# SCH_Roboliga_2026_Futbol_2026-04-12.net
KiCad netlist of a schematic drawn in EasyEDA
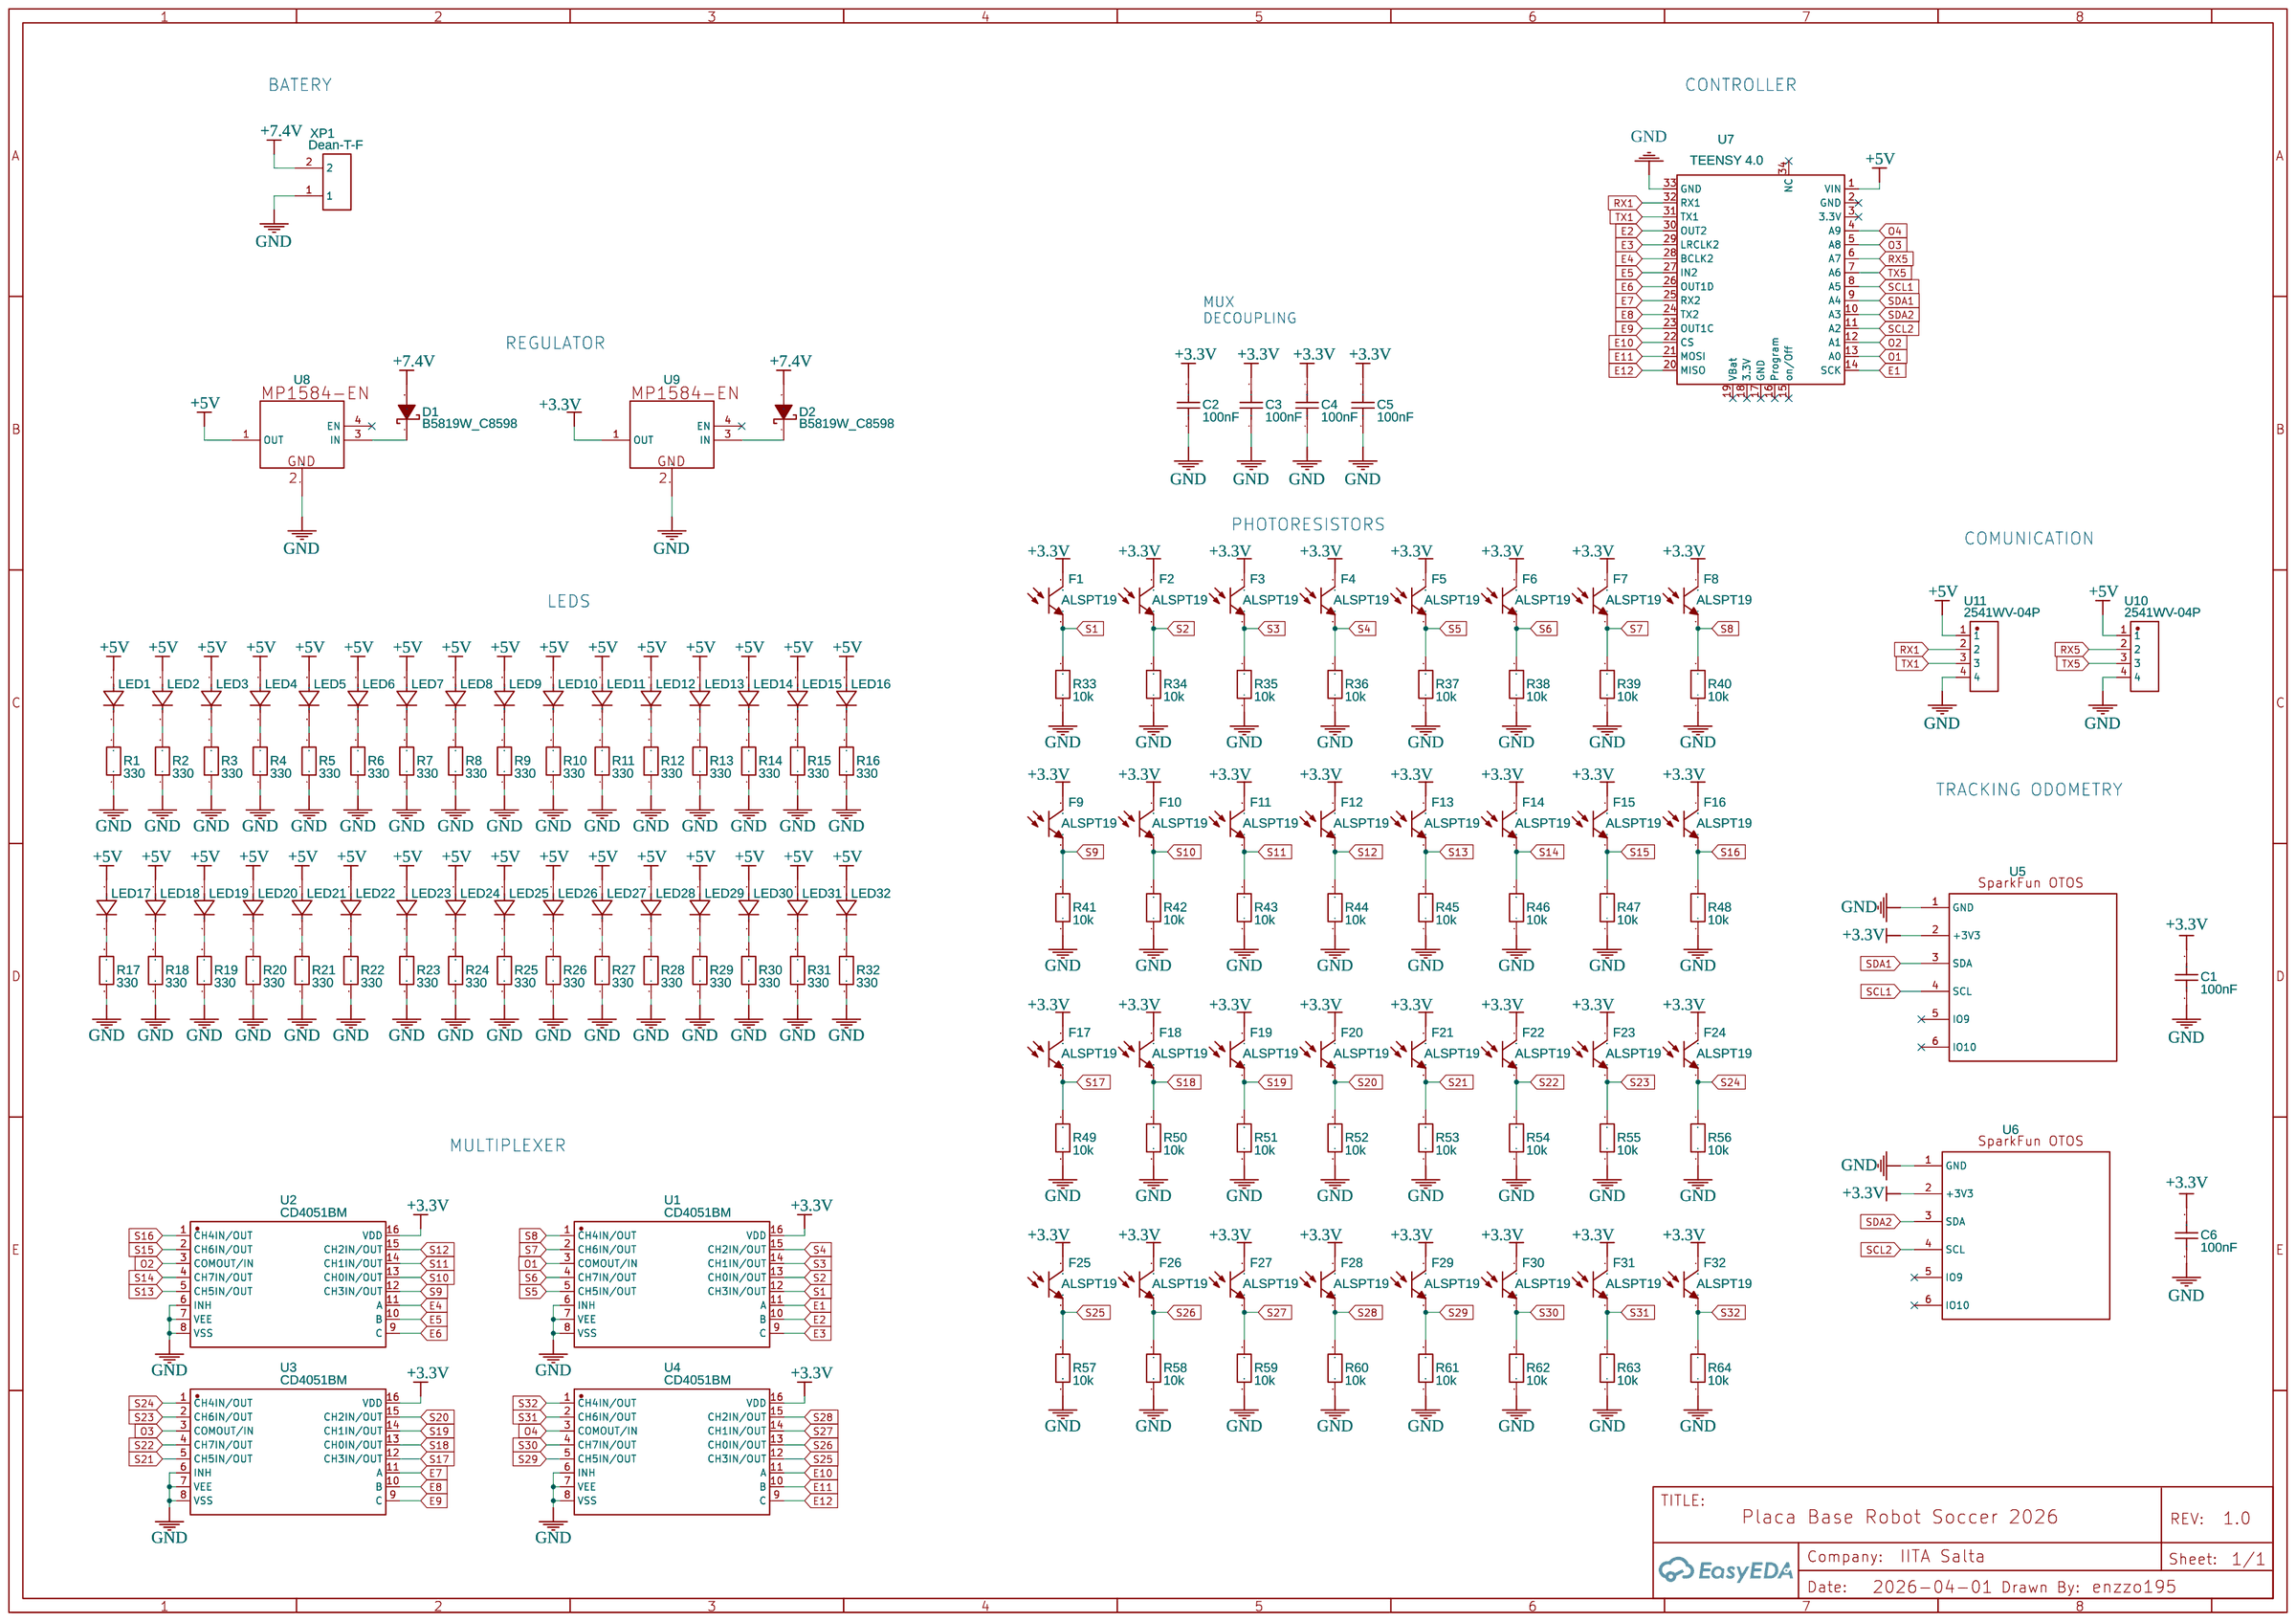
[diagram p0: schematic sheet]

(export (version "E")
  (design (tool "Eeschema 10.0.6"))
  (components
    (comp (ref "C1") (value "100nF") (libsource (lib "") (part "C_0603_US")))
    (comp (ref "C2") (value "100nF") (libsource (lib "") (part "C_0603_US")))
    (comp (ref "C3") (value "100nF") (libsource (lib "") (part "C_0603_US")))
    (comp (ref "C4") (value "100nF") (libsource (lib "") (part "C_0603_US")))
    (comp (ref "C5") (value "100nF") (libsource (lib "") (part "C_0603_US")))
    (comp (ref "C6") (value "100nF") (libsource (lib "") (part "C_0603_US")))
    (comp (ref "D1")
      (value "B5819W_C8598")
      (fields (field (name "Manufacturer Part") "B5819W SL") (field (name "Manufacturer") "CJ(江苏长电/长晶)"))
      (libsource (lib "") (part "B5819W_C8598"))
    )
    (comp (ref "D2")
      (value "B5819W_C8598")
      (fields (field (name "Manufacturer Part") "B5819W SL") (field (name "Manufacturer") "CJ(江苏长电/长晶)"))
      (libsource (lib "") (part "B5819W_C8598"))
    )
    (comp (ref "F1")
      (value "ALSPT19")
      (fields
        (field (name "Manufacturer Part") "ALS-PT19-315C/L177/TR8")
        (field (name "Manufacturer") "EVERLIGHT(亿光)")
      )
      (libsource (lib "") (part "ALS-PT19-315C/L177/TR8"))
    )
    (comp (ref "F2")
      (value "ALSPT19")
      (fields
        (field (name "Manufacturer Part") "ALS-PT19-315C/L177/TR8")
        (field (name "Manufacturer") "EVERLIGHT(亿光)")
      )
      (libsource (lib "") (part "ALS-PT19-315C/L177/TR8"))
    )
    (comp (ref "F3")
      (value "ALSPT19")
      (fields
        (field (name "Manufacturer Part") "ALS-PT19-315C/L177/TR8")
        (field (name "Manufacturer") "EVERLIGHT(亿光)")
      )
      (libsource (lib "") (part "ALS-PT19-315C/L177/TR8"))
    )
    (comp (ref "F4")
      (value "ALSPT19")
      (fields
        (field (name "Manufacturer Part") "ALS-PT19-315C/L177/TR8")
        (field (name "Manufacturer") "EVERLIGHT(亿光)")
      )
      (libsource (lib "") (part "ALS-PT19-315C/L177/TR8"))
    )
    (comp (ref "F5")
      (value "ALSPT19")
      (fields
        (field (name "Manufacturer Part") "ALS-PT19-315C/L177/TR8")
        (field (name "Manufacturer") "EVERLIGHT(亿光)")
      )
      (libsource (lib "") (part "ALS-PT19-315C/L177/TR8"))
    )
    (comp (ref "F6")
      (value "ALSPT19")
      (fields
        (field (name "Manufacturer Part") "ALS-PT19-315C/L177/TR8")
        (field (name "Manufacturer") "EVERLIGHT(亿光)")
      )
      (libsource (lib "") (part "ALS-PT19-315C/L177/TR8"))
    )
    (comp (ref "F7")
      (value "ALSPT19")
      (fields
        (field (name "Manufacturer Part") "ALS-PT19-315C/L177/TR8")
        (field (name "Manufacturer") "EVERLIGHT(亿光)")
      )
      (libsource (lib "") (part "ALS-PT19-315C/L177/TR8"))
    )
    (comp (ref "F8")
      (value "ALSPT19")
      (fields
        (field (name "Manufacturer Part") "ALS-PT19-315C/L177/TR8")
        (field (name "Manufacturer") "EVERLIGHT(亿光)")
      )
      (libsource (lib "") (part "ALS-PT19-315C/L177/TR8"))
    )
    (comp (ref "F9")
      (value "ALSPT19")
      (fields
        (field (name "Manufacturer Part") "ALS-PT19-315C/L177/TR8")
        (field (name "Manufacturer") "EVERLIGHT(亿光)")
      )
      (libsource (lib "") (part "ALS-PT19-315C/L177/TR8"))
    )
    (comp (ref "F10")
      (value "ALSPT19")
      (fields
        (field (name "Manufacturer Part") "ALS-PT19-315C/L177/TR8")
        (field (name "Manufacturer") "EVERLIGHT(亿光)")
      )
      (libsource (lib "") (part "ALS-PT19-315C/L177/TR8"))
    )
    (comp (ref "F11")
      (value "ALSPT19")
      (fields
        (field (name "Manufacturer Part") "ALS-PT19-315C/L177/TR8")
        (field (name "Manufacturer") "EVERLIGHT(亿光)")
      )
      (libsource (lib "") (part "ALS-PT19-315C/L177/TR8"))
    )
    (comp (ref "F12")
      (value "ALSPT19")
      (fields
        (field (name "Manufacturer Part") "ALS-PT19-315C/L177/TR8")
        (field (name "Manufacturer") "EVERLIGHT(亿光)")
      )
      (libsource (lib "") (part "ALS-PT19-315C/L177/TR8"))
    )
    (comp (ref "F13")
      (value "ALSPT19")
      (fields
        (field (name "Manufacturer Part") "ALS-PT19-315C/L177/TR8")
        (field (name "Manufacturer") "EVERLIGHT(亿光)")
      )
      (libsource (lib "") (part "ALS-PT19-315C/L177/TR8"))
    )
    (comp (ref "F14")
      (value "ALSPT19")
      (fields
        (field (name "Manufacturer Part") "ALS-PT19-315C/L177/TR8")
        (field (name "Manufacturer") "EVERLIGHT(亿光)")
      )
      (libsource (lib "") (part "ALS-PT19-315C/L177/TR8"))
    )
    (comp (ref "F15")
      (value "ALSPT19")
      (fields
        (field (name "Manufacturer Part") "ALS-PT19-315C/L177/TR8")
        (field (name "Manufacturer") "EVERLIGHT(亿光)")
      )
      (libsource (lib "") (part "ALS-PT19-315C/L177/TR8"))
    )
    (comp (ref "F16")
      (value "ALSPT19")
      (fields
        (field (name "Manufacturer Part") "ALS-PT19-315C/L177/TR8")
        (field (name "Manufacturer") "EVERLIGHT(亿光)")
      )
      (libsource (lib "") (part "ALS-PT19-315C/L177/TR8"))
    )
    (comp (ref "F17")
      (value "ALSPT19")
      (fields
        (field (name "Manufacturer Part") "ALS-PT19-315C/L177/TR8")
        (field (name "Manufacturer") "EVERLIGHT(亿光)")
      )
      (libsource (lib "") (part "ALS-PT19-315C/L177/TR8"))
    )
    (comp (ref "F18")
      (value "ALSPT19")
      (fields
        (field (name "Manufacturer Part") "ALS-PT19-315C/L177/TR8")
        (field (name "Manufacturer") "EVERLIGHT(亿光)")
      )
      (libsource (lib "") (part "ALS-PT19-315C/L177/TR8"))
    )
    (comp (ref "F19")
      (value "ALSPT19")
      (fields
        (field (name "Manufacturer Part") "ALS-PT19-315C/L177/TR8")
        (field (name "Manufacturer") "EVERLIGHT(亿光)")
      )
      (libsource (lib "") (part "ALS-PT19-315C/L177/TR8"))
    )
    (comp (ref "F20")
      (value "ALSPT19")
      (fields
        (field (name "Manufacturer Part") "ALS-PT19-315C/L177/TR8")
        (field (name "Manufacturer") "EVERLIGHT(亿光)")
      )
      (libsource (lib "") (part "ALS-PT19-315C/L177/TR8"))
    )
    (comp (ref "F21")
      (value "ALSPT19")
      (fields
        (field (name "Manufacturer Part") "ALS-PT19-315C/L177/TR8")
        (field (name "Manufacturer") "EVERLIGHT(亿光)")
      )
      (libsource (lib "") (part "ALS-PT19-315C/L177/TR8"))
    )
    (comp (ref "F22")
      (value "ALSPT19")
      (fields
        (field (name "Manufacturer Part") "ALS-PT19-315C/L177/TR8")
        (field (name "Manufacturer") "EVERLIGHT(亿光)")
      )
      (libsource (lib "") (part "ALS-PT19-315C/L177/TR8"))
    )
    (comp (ref "F23")
      (value "ALSPT19")
      (fields
        (field (name "Manufacturer Part") "ALS-PT19-315C/L177/TR8")
        (field (name "Manufacturer") "EVERLIGHT(亿光)")
      )
      (libsource (lib "") (part "ALS-PT19-315C/L177/TR8"))
    )
    (comp (ref "F24")
      (value "ALSPT19")
      (fields
        (field (name "Manufacturer Part") "ALS-PT19-315C/L177/TR8")
        (field (name "Manufacturer") "EVERLIGHT(亿光)")
      )
      (libsource (lib "") (part "ALS-PT19-315C/L177/TR8"))
    )
    (comp (ref "F25")
      (value "ALSPT19")
      (fields
        (field (name "Manufacturer Part") "ALS-PT19-315C/L177/TR8")
        (field (name "Manufacturer") "EVERLIGHT(亿光)")
      )
      (libsource (lib "") (part "ALS-PT19-315C/L177/TR8"))
    )
    (comp (ref "F26")
      (value "ALSPT19")
      (fields
        (field (name "Manufacturer Part") "ALS-PT19-315C/L177/TR8")
        (field (name "Manufacturer") "EVERLIGHT(亿光)")
      )
      (libsource (lib "") (part "ALS-PT19-315C/L177/TR8"))
    )
    (comp (ref "F27")
      (value "ALSPT19")
      (fields
        (field (name "Manufacturer Part") "ALS-PT19-315C/L177/TR8")
        (field (name "Manufacturer") "EVERLIGHT(亿光)")
      )
      (libsource (lib "") (part "ALS-PT19-315C/L177/TR8"))
    )
    (comp (ref "F28")
      (value "ALSPT19")
      (fields
        (field (name "Manufacturer Part") "ALS-PT19-315C/L177/TR8")
        (field (name "Manufacturer") "EVERLIGHT(亿光)")
      )
      (libsource (lib "") (part "ALS-PT19-315C/L177/TR8"))
    )
    (comp (ref "F29")
      (value "ALSPT19")
      (fields
        (field (name "Manufacturer Part") "ALS-PT19-315C/L177/TR8")
        (field (name "Manufacturer") "EVERLIGHT(亿光)")
      )
      (libsource (lib "") (part "ALS-PT19-315C/L177/TR8"))
    )
    (comp (ref "F30")
      (value "ALSPT19")
      (fields
        (field (name "Manufacturer Part") "ALS-PT19-315C/L177/TR8")
        (field (name "Manufacturer") "EVERLIGHT(亿光)")
      )
      (libsource (lib "") (part "ALS-PT19-315C/L177/TR8"))
    )
    (comp (ref "F31")
      (value "ALSPT19")
      (fields
        (field (name "Manufacturer Part") "ALS-PT19-315C/L177/TR8")
        (field (name "Manufacturer") "EVERLIGHT(亿光)")
      )
      (libsource (lib "") (part "ALS-PT19-315C/L177/TR8"))
    )
    (comp (ref "F32")
      (value "ALSPT19")
      (fields
        (field (name "Manufacturer Part") "ALS-PT19-315C/L177/TR8")
        (field (name "Manufacturer") "EVERLIGHT(亿光)")
      )
      (libsource (lib "") (part "ALS-PT19-315C/L177/TR8"))
    )
    (comp (ref "LED1")
      (value "LED402O")
      (fields (field (name "Manufacturer Part") "YLED0402O") (field (name "Manufacturer") "YONGYUTAI(永裕泰)"))
      (libsource (lib "") (part "YLED0402O"))
    )
    (comp (ref "LED2")
      (value "LED402O")
      (fields (field (name "Manufacturer Part") "YLED0402O") (field (name "Manufacturer") "YONGYUTAI(永裕泰)"))
      (libsource (lib "") (part "YLED0402O"))
    )
    (comp (ref "LED3")
      (value "LED402O")
      (fields (field (name "Manufacturer Part") "YLED0402O") (field (name "Manufacturer") "YONGYUTAI(永裕泰)"))
      (libsource (lib "") (part "YLED0402O"))
    )
    (comp (ref "LED4")
      (value "LED402O")
      (fields (field (name "Manufacturer Part") "YLED0402O") (field (name "Manufacturer") "YONGYUTAI(永裕泰)"))
      (libsource (lib "") (part "YLED0402O"))
    )
    (comp (ref "LED5")
      (value "LED402O")
      (fields (field (name "Manufacturer Part") "YLED0402O") (field (name "Manufacturer") "YONGYUTAI(永裕泰)"))
      (libsource (lib "") (part "YLED0402O"))
    )
    (comp (ref "LED6")
      (value "LED402O")
      (fields (field (name "Manufacturer Part") "YLED0402O") (field (name "Manufacturer") "YONGYUTAI(永裕泰)"))
      (libsource (lib "") (part "YLED0402O"))
    )
    (comp (ref "LED7")
      (value "LED402O")
      (fields (field (name "Manufacturer Part") "YLED0402O") (field (name "Manufacturer") "YONGYUTAI(永裕泰)"))
      (libsource (lib "") (part "YLED0402O"))
    )
    (comp (ref "LED8")
      (value "LED402O")
      (fields (field (name "Manufacturer Part") "YLED0402O") (field (name "Manufacturer") "YONGYUTAI(永裕泰)"))
      (libsource (lib "") (part "YLED0402O"))
    )
    (comp (ref "LED9")
      (value "LED402O")
      (fields (field (name "Manufacturer Part") "YLED0402O") (field (name "Manufacturer") "YONGYUTAI(永裕泰)"))
      (libsource (lib "") (part "YLED0402O"))
    )
    (comp (ref "LED10")
      (value "LED402O")
      (fields (field (name "Manufacturer Part") "YLED0402O") (field (name "Manufacturer") "YONGYUTAI(永裕泰)"))
      (libsource (lib "") (part "YLED0402O"))
    )
    (comp (ref "LED11")
      (value "LED402O")
      (fields (field (name "Manufacturer Part") "YLED0402O") (field (name "Manufacturer") "YONGYUTAI(永裕泰)"))
      (libsource (lib "") (part "YLED0402O"))
    )
    (comp (ref "LED12")
      (value "LED402O")
      (fields (field (name "Manufacturer Part") "YLED0402O") (field (name "Manufacturer") "YONGYUTAI(永裕泰)"))
      (libsource (lib "") (part "YLED0402O"))
    )
    (comp (ref "LED13")
      (value "LED402O")
      (fields (field (name "Manufacturer Part") "YLED0402O") (field (name "Manufacturer") "YONGYUTAI(永裕泰)"))
      (libsource (lib "") (part "YLED0402O"))
    )
    (comp (ref "LED14")
      (value "LED402O")
      (fields (field (name "Manufacturer Part") "YLED0402O") (field (name "Manufacturer") "YONGYUTAI(永裕泰)"))
      (libsource (lib "") (part "YLED0402O"))
    )
    (comp (ref "LED15")
      (value "LED402O")
      (fields (field (name "Manufacturer Part") "YLED0402O") (field (name "Manufacturer") "YONGYUTAI(永裕泰)"))
      (libsource (lib "") (part "YLED0402O"))
    )
    (comp (ref "LED16")
      (value "LED402O")
      (fields (field (name "Manufacturer Part") "YLED0402O") (field (name "Manufacturer") "YONGYUTAI(永裕泰)"))
      (libsource (lib "") (part "YLED0402O"))
    )
    (comp (ref "LED17")
      (value "LED402O")
      (fields (field (name "Manufacturer Part") "YLED0402O") (field (name "Manufacturer") "YONGYUTAI(永裕泰)"))
      (libsource (lib "") (part "YLED0402O"))
    )
    (comp (ref "LED18")
      (value "LED402O")
      (fields (field (name "Manufacturer Part") "YLED0402O") (field (name "Manufacturer") "YONGYUTAI(永裕泰)"))
      (libsource (lib "") (part "YLED0402O"))
    )
    (comp (ref "LED19")
      (value "LED402O")
      (fields (field (name "Manufacturer Part") "YLED0402O") (field (name "Manufacturer") "YONGYUTAI(永裕泰)"))
      (libsource (lib "") (part "YLED0402O"))
    )
    (comp (ref "LED20")
      (value "LED402O")
      (fields (field (name "Manufacturer Part") "YLED0402O") (field (name "Manufacturer") "YONGYUTAI(永裕泰)"))
      (libsource (lib "") (part "YLED0402O"))
    )
    (comp (ref "LED21")
      (value "LED402O")
      (fields (field (name "Manufacturer Part") "YLED0402O") (field (name "Manufacturer") "YONGYUTAI(永裕泰)"))
      (libsource (lib "") (part "YLED0402O"))
    )
    (comp (ref "LED22")
      (value "LED402O")
      (fields (field (name "Manufacturer Part") "YLED0402O") (field (name "Manufacturer") "YONGYUTAI(永裕泰)"))
      (libsource (lib "") (part "YLED0402O"))
    )
    (comp (ref "LED23")
      (value "LED402O")
      (fields (field (name "Manufacturer Part") "YLED0402O") (field (name "Manufacturer") "YONGYUTAI(永裕泰)"))
      (libsource (lib "") (part "YLED0402O"))
    )
    (comp (ref "LED24")
      (value "LED402O")
      (fields (field (name "Manufacturer Part") "YLED0402O") (field (name "Manufacturer") "YONGYUTAI(永裕泰)"))
      (libsource (lib "") (part "YLED0402O"))
    )
    (comp (ref "LED25")
      (value "LED402O")
      (fields (field (name "Manufacturer Part") "YLED0402O") (field (name "Manufacturer") "YONGYUTAI(永裕泰)"))
      (libsource (lib "") (part "YLED0402O"))
    )
    (comp (ref "LED26")
      (value "LED402O")
      (fields (field (name "Manufacturer Part") "YLED0402O") (field (name "Manufacturer") "YONGYUTAI(永裕泰)"))
      (libsource (lib "") (part "YLED0402O"))
    )
    (comp (ref "LED27")
      (value "LED402O")
      (fields (field (name "Manufacturer Part") "YLED0402O") (field (name "Manufacturer") "YONGYUTAI(永裕泰)"))
      (libsource (lib "") (part "YLED0402O"))
    )
    (comp (ref "LED28")
      (value "LED402O")
      (fields (field (name "Manufacturer Part") "YLED0402O") (field (name "Manufacturer") "YONGYUTAI(永裕泰)"))
      (libsource (lib "") (part "YLED0402O"))
    )
    (comp (ref "LED29")
      (value "LED402O")
      (fields (field (name "Manufacturer Part") "YLED0402O") (field (name "Manufacturer") "YONGYUTAI(永裕泰)"))
      (libsource (lib "") (part "YLED0402O"))
    )
    (comp (ref "LED30")
      (value "LED402O")
      (fields (field (name "Manufacturer Part") "YLED0402O") (field (name "Manufacturer") "YONGYUTAI(永裕泰)"))
      (libsource (lib "") (part "YLED0402O"))
    )
    (comp (ref "LED31")
      (value "LED402O")
      (fields (field (name "Manufacturer Part") "YLED0402O") (field (name "Manufacturer") "YONGYUTAI(永裕泰)"))
      (libsource (lib "") (part "YLED0402O"))
    )
    (comp (ref "LED32")
      (value "LED402O")
      (fields (field (name "Manufacturer Part") "YLED0402O") (field (name "Manufacturer") "YONGYUTAI(永裕泰)"))
      (libsource (lib "") (part "YLED0402O"))
    )
    (comp (ref "R1") (value "330") (libsource (lib "") (part "R_0603_EU")))
    (comp (ref "R2") (value "330") (libsource (lib "") (part "R_0603_EU")))
    (comp (ref "R3") (value "330") (libsource (lib "") (part "R_0603_EU")))
    (comp (ref "R4") (value "330") (libsource (lib "") (part "R_0603_EU")))
    (comp (ref "R5") (value "330") (libsource (lib "") (part "R_0603_EU")))
    (comp (ref "R6") (value "330") (libsource (lib "") (part "R_0603_EU")))
    (comp (ref "R7") (value "330") (libsource (lib "") (part "R_0603_EU")))
    (comp (ref "R8") (value "330") (libsource (lib "") (part "R_0603_EU")))
    (comp (ref "R9") (value "330") (libsource (lib "") (part "R_0603_EU")))
    (comp (ref "R10") (value "330") (libsource (lib "") (part "R_0603_EU")))
    (comp (ref "R11") (value "330") (libsource (lib "") (part "R_0603_EU")))
    (comp (ref "R12") (value "330") (libsource (lib "") (part "R_0603_EU")))
    (comp (ref "R13") (value "330") (libsource (lib "") (part "R_0603_EU")))
    (comp (ref "R14") (value "330") (libsource (lib "") (part "R_0603_EU")))
    (comp (ref "R15") (value "330") (libsource (lib "") (part "R_0603_EU")))
    (comp (ref "R16") (value "330") (libsource (lib "") (part "R_0603_EU")))
    (comp (ref "R17") (value "330") (libsource (lib "") (part "R_0603_EU")))
    (comp (ref "R18") (value "330") (libsource (lib "") (part "R_0603_EU")))
    (comp (ref "R19") (value "330") (libsource (lib "") (part "R_0603_EU")))
    (comp (ref "R20") (value "330") (libsource (lib "") (part "R_0603_EU")))
    (comp (ref "R21") (value "330") (libsource (lib "") (part "R_0603_EU")))
    (comp (ref "R22") (value "330") (libsource (lib "") (part "R_0603_EU")))
    (comp (ref "R23") (value "330") (libsource (lib "") (part "R_0603_EU")))
    (comp (ref "R24") (value "330") (libsource (lib "") (part "R_0603_EU")))
    (comp (ref "R25") (value "330") (libsource (lib "") (part "R_0603_EU")))
    (comp (ref "R26") (value "330") (libsource (lib "") (part "R_0603_EU")))
    (comp (ref "R27") (value "330") (libsource (lib "") (part "R_0603_EU")))
    (comp (ref "R28") (value "330") (libsource (lib "") (part "R_0603_EU")))
    (comp (ref "R29") (value "330") (libsource (lib "") (part "R_0603_EU")))
    (comp (ref "R30") (value "330") (libsource (lib "") (part "R_0603_EU")))
    (comp (ref "R31") (value "330") (libsource (lib "") (part "R_0603_EU")))
    (comp (ref "R32") (value "330") (libsource (lib "") (part "R_0603_EU")))
    (comp (ref "R33") (value "10k") (libsource (lib "") (part "R_0603_EU")))
    (comp (ref "R34") (value "10k") (libsource (lib "") (part "R_0603_EU")))
    (comp (ref "R35") (value "10k") (libsource (lib "") (part "R_0603_EU")))
    (comp (ref "R36") (value "10k") (libsource (lib "") (part "R_0603_EU")))
    (comp (ref "R37") (value "10k") (libsource (lib "") (part "R_0603_EU")))
    (comp (ref "R38") (value "10k") (libsource (lib "") (part "R_0603_EU")))
    (comp (ref "R39") (value "10k") (libsource (lib "") (part "R_0603_EU")))
    (comp (ref "R40") (value "10k") (libsource (lib "") (part "R_0603_EU")))
    (comp (ref "R41") (value "10k") (libsource (lib "") (part "R_0603_EU")))
    (comp (ref "R42") (value "10k") (libsource (lib "") (part "R_0603_EU")))
    (comp (ref "R43") (value "10k") (libsource (lib "") (part "R_0603_EU")))
    (comp (ref "R44") (value "10k") (libsource (lib "") (part "R_0603_EU")))
    (comp (ref "R45") (value "10k") (libsource (lib "") (part "R_0603_EU")))
    (comp (ref "R46") (value "10k") (libsource (lib "") (part "R_0603_EU")))
    (comp (ref "R47") (value "10k") (libsource (lib "") (part "R_0603_EU")))
    (comp (ref "R48") (value "10k") (libsource (lib "") (part "R_0603_EU")))
    (comp (ref "R49") (value "10k") (libsource (lib "") (part "R_0603_EU")))
    (comp (ref "R50") (value "10k") (libsource (lib "") (part "R_0603_EU")))
    (comp (ref "R51") (value "10k") (libsource (lib "") (part "R_0603_EU")))
    (comp (ref "R52") (value "10k") (libsource (lib "") (part "R_0603_EU")))
    (comp (ref "R53") (value "10k") (libsource (lib "") (part "R_0603_EU")))
    (comp (ref "R54") (value "10k") (libsource (lib "") (part "R_0603_EU")))
    (comp (ref "R55") (value "10k") (libsource (lib "") (part "R_0603_EU")))
    (comp (ref "R56") (value "10k") (libsource (lib "") (part "R_0603_EU")))
    (comp (ref "R57") (value "10k") (libsource (lib "") (part "R_0603_EU")))
    (comp (ref "R58") (value "10k") (libsource (lib "") (part "R_0603_EU")))
    (comp (ref "R59") (value "10k") (libsource (lib "") (part "R_0603_EU")))
    (comp (ref "R60") (value "10k") (libsource (lib "") (part "R_0603_EU")))
    (comp (ref "R61") (value "10k") (libsource (lib "") (part "R_0603_EU")))
    (comp (ref "R62") (value "10k") (libsource (lib "") (part "R_0603_EU")))
    (comp (ref "R63") (value "10k") (libsource (lib "") (part "R_0603_EU")))
    (comp (ref "R64") (value "10k") (libsource (lib "") (part "R_0603_EU")))
    (comp (ref "U1")
      (value "CD4051BM")
      (fields (field (name "Manufacturer") "TI(德州仪器)"))
      (libsource (lib "") (part "CD4051BM"))
    )
    (comp (ref "U2")
      (value "CD4051BM")
      (fields (field (name "Manufacturer") "TI(德州仪器)"))
      (libsource (lib "") (part "CD4051BM"))
    )
    (comp (ref "U3")
      (value "CD4051BM")
      (fields (field (name "Manufacturer") "TI(德州仪器)"))
      (libsource (lib "") (part "CD4051BM"))
    )
    (comp (ref "U4")
      (value "CD4051BM")
      (fields (field (name "Manufacturer") "TI(德州仪器)"))
      (libsource (lib "") (part "CD4051BM"))
    )
    (comp (ref "U5")
      (value "SparkFun OTOS")
      (fields (field (name "Manufacturer") "Sparkfun"))
      (libsource (lib "") (part "SparkFun OTOS"))
    )
    (comp (ref "U6")
      (value "SparkFun OTOS")
      (fields (field (name "Manufacturer") "Sparkfun"))
      (libsource (lib "") (part "SparkFun OTOS_1"))
    )
    (comp (ref "U7")
      (value "TEENSY 4.0")
      (fields (field (name "Manufacturer Part") "Teensy 4.0"))
      (libsource (lib "") (part "TEENSY 4.0"))
    )
    (comp (ref "U8")
      (value "MP1584EN 4-Pin SIP Module")
      (libsource (lib "") (part "MP1584EN 4-Pin SIP Module"))
    )
    (comp (ref "U9")
      (value "MP1584EN 4-Pin SIP Module")
      (libsource (lib "") (part "MP1584EN 4-Pin SIP Module"))
    )
    (comp (ref "U10")
      (value "2541WV-04P")
      (fields (field (name "Manufacturer") "HanElectricity(瀚源)"))
      (libsource (lib "") (part "2541WV-04P"))
    )
    (comp (ref "U11")
      (value "2541WV-04P")
      (fields (field (name "Manufacturer") "HanElectricity(瀚源)"))
      (libsource (lib "") (part "2541WV-04P"))
    )
    (comp (ref "XP1") (value "Dean-T-F") (libsource (lib "") (part "Dean-T-F")))
  )
  (nets
    (net (code "1") (name "+3.3V") (class "Default")
      (node (ref "C1") (pin "2") (pinfunction "2_2") (pintype "unspecified"))
      (node (ref "C2") (pin "2") (pinfunction "2_2") (pintype "unspecified"))
      (node (ref "C3") (pin "2") (pinfunction "2_2") (pintype "unspecified"))
      (node (ref "C4") (pin "2") (pinfunction "2_2") (pintype "unspecified"))
      (node (ref "C5") (pin "2") (pinfunction "2_2") (pintype "unspecified"))
      (node (ref "C6") (pin "2") (pinfunction "2_2") (pintype "unspecified"))
      (node (ref "F1") (pin "1") (pinfunction "C_1") (pintype "input"))
      (node (ref "F10") (pin "1") (pinfunction "C_1") (pintype "input"))
      (node (ref "F11") (pin "1") (pinfunction "C_1") (pintype "input"))
      (node (ref "F12") (pin "1") (pinfunction "C_1") (pintype "input"))
      (node (ref "F13") (pin "1") (pinfunction "C_1") (pintype "input"))
      (node (ref "F14") (pin "1") (pinfunction "C_1") (pintype "input"))
      (node (ref "F15") (pin "1") (pinfunction "C_1") (pintype "input"))
      (node (ref "F16") (pin "1") (pinfunction "C_1") (pintype "input"))
      (node (ref "F17") (pin "1") (pinfunction "C_1") (pintype "input"))
      (node (ref "F18") (pin "1") (pinfunction "C_1") (pintype "input"))
      (node (ref "F19") (pin "1") (pinfunction "C_1") (pintype "input"))
      (node (ref "F2") (pin "1") (pinfunction "C_1") (pintype "input"))
      (node (ref "F20") (pin "1") (pinfunction "C_1") (pintype "input"))
      (node (ref "F21") (pin "1") (pinfunction "C_1") (pintype "input"))
      (node (ref "F22") (pin "1") (pinfunction "C_1") (pintype "input"))
      (node (ref "F23") (pin "1") (pinfunction "C_1") (pintype "input"))
      (node (ref "F24") (pin "1") (pinfunction "C_1") (pintype "input"))
      (node (ref "F25") (pin "1") (pinfunction "C_1") (pintype "input"))
      (node (ref "F26") (pin "1") (pinfunction "C_1") (pintype "input"))
      (node (ref "F27") (pin "1") (pinfunction "C_1") (pintype "input"))
      (node (ref "F28") (pin "1") (pinfunction "C_1") (pintype "input"))
      (node (ref "F29") (pin "1") (pinfunction "C_1") (pintype "input"))
      (node (ref "F3") (pin "1") (pinfunction "C_1") (pintype "input"))
      (node (ref "F30") (pin "1") (pinfunction "C_1") (pintype "input"))
      (node (ref "F31") (pin "1") (pinfunction "C_1") (pintype "input"))
      (node (ref "F32") (pin "1") (pinfunction "C_1") (pintype "input"))
      (node (ref "F4") (pin "1") (pinfunction "C_1") (pintype "input"))
      (node (ref "F5") (pin "1") (pinfunction "C_1") (pintype "input"))
      (node (ref "F6") (pin "1") (pinfunction "C_1") (pintype "input"))
      (node (ref "F7") (pin "1") (pinfunction "C_1") (pintype "input"))
      (node (ref "F8") (pin "1") (pinfunction "C_1") (pintype "input"))
      (node (ref "F9") (pin "1") (pinfunction "C_1") (pintype "input"))
      (node (ref "U1") (pin "16") (pinfunction "VDD_16") (pintype "unspecified"))
      (node (ref "U2") (pin "16") (pinfunction "VDD_16") (pintype "unspecified"))
      (node (ref "U3") (pin "16") (pinfunction "VDD_16") (pintype "unspecified"))
      (node (ref "U4") (pin "16") (pinfunction "VDD_16") (pintype "unspecified"))
      (node (ref "U5") (pin "2") (pinfunction "+3V3_2") (pintype "unspecified"))
      (node (ref "U6") (pin "2") (pinfunction "+3V3_2") (pintype "unspecified"))
      (node (ref "U9") (pin "1") (pinfunction "OUT_1") (pintype "unspecified"))
    )
    (net (code "2") (name "+5V") (class "Default")
      (node (ref "LED1") (pin "1") (pinfunction "A_1") (pintype "unspecified"))
      (node (ref "LED10") (pin "1") (pinfunction "A_1") (pintype "unspecified"))
      (node (ref "LED11") (pin "1") (pinfunction "A_1") (pintype "unspecified"))
      (node (ref "LED12") (pin "1") (pinfunction "A_1") (pintype "unspecified"))
      (node (ref "LED13") (pin "1") (pinfunction "A_1") (pintype "unspecified"))
      (node (ref "LED14") (pin "1") (pinfunction "A_1") (pintype "unspecified"))
      (node (ref "LED15") (pin "1") (pinfunction "A_1") (pintype "unspecified"))
      (node (ref "LED16") (pin "1") (pinfunction "A_1") (pintype "unspecified"))
      (node (ref "LED17") (pin "1") (pinfunction "A_1") (pintype "unspecified"))
      (node (ref "LED18") (pin "1") (pinfunction "A_1") (pintype "unspecified"))
      (node (ref "LED19") (pin "1") (pinfunction "A_1") (pintype "unspecified"))
      (node (ref "LED2") (pin "1") (pinfunction "A_1") (pintype "unspecified"))
      (node (ref "LED20") (pin "1") (pinfunction "A_1") (pintype "unspecified"))
      (node (ref "LED21") (pin "1") (pinfunction "A_1") (pintype "unspecified"))
      (node (ref "LED22") (pin "1") (pinfunction "A_1") (pintype "unspecified"))
      (node (ref "LED23") (pin "1") (pinfunction "A_1") (pintype "unspecified"))
      (node (ref "LED24") (pin "1") (pinfunction "A_1") (pintype "unspecified"))
      (node (ref "LED25") (pin "1") (pinfunction "A_1") (pintype "unspecified"))
      (node (ref "LED26") (pin "1") (pinfunction "A_1") (pintype "unspecified"))
      (node (ref "LED27") (pin "1") (pinfunction "A_1") (pintype "unspecified"))
      (node (ref "LED28") (pin "1") (pinfunction "A_1") (pintype "unspecified"))
      (node (ref "LED29") (pin "1") (pinfunction "A_1") (pintype "unspecified"))
      (node (ref "LED3") (pin "1") (pinfunction "A_1") (pintype "unspecified"))
      (node (ref "LED30") (pin "1") (pinfunction "A_1") (pintype "unspecified"))
      (node (ref "LED31") (pin "1") (pinfunction "A_1") (pintype "unspecified"))
      (node (ref "LED32") (pin "1") (pinfunction "A_1") (pintype "unspecified"))
      (node (ref "LED4") (pin "1") (pinfunction "A_1") (pintype "unspecified"))
      (node (ref "LED5") (pin "1") (pinfunction "A_1") (pintype "unspecified"))
      (node (ref "LED6") (pin "1") (pinfunction "A_1") (pintype "unspecified"))
      (node (ref "LED7") (pin "1") (pinfunction "A_1") (pintype "unspecified"))
      (node (ref "LED8") (pin "1") (pinfunction "A_1") (pintype "unspecified"))
      (node (ref "LED9") (pin "1") (pinfunction "A_1") (pintype "unspecified"))
      (node (ref "U10") (pin "1") (pinfunction "1_1") (pintype "unspecified"))
      (node (ref "U11") (pin "1") (pinfunction "1_1") (pintype "unspecified"))
      (node (ref "U7") (pin "1") (pinfunction "VIN_1") (pintype "unspecified"))
      (node (ref "U8") (pin "1") (pinfunction "OUT_1") (pintype "unspecified"))
    )
    (net (code "3") (name "+7.4V") (class "Default")
      (node (ref "D1") (pin "2") (pinfunction "+_2") (pintype "unspecified"))
      (node (ref "D2") (pin "2") (pinfunction "+_2") (pintype "unspecified"))
      (node (ref "XP1") (pin "2") (pinfunction "2_2") (pintype "unspecified"))
    )
    (net (code "4") (name "E1") (class "Default")
      (node (ref "U1") (pin "11") (pinfunction "A_11") (pintype "unspecified"))
      (node (ref "U7") (pin "14") (pinfunction "SCK_14") (pintype "unspecified"))
    )
    (net (code "5") (name "E2") (class "Default")
      (node (ref "U1") (pin "10") (pinfunction "B_10") (pintype "unspecified"))
      (node (ref "U7") (pin "30") (pinfunction "OUT2_30") (pintype "unspecified"))
    )
    (net (code "6") (name "E3") (class "Default")
      (node (ref "U1") (pin "9") (pinfunction "C_9") (pintype "unspecified"))
      (node (ref "U7") (pin "29") (pinfunction "LRCLK2_29") (pintype "unspecified"))
    )
    (net (code "7") (name "E4") (class "Default")
      (node (ref "U2") (pin "11") (pinfunction "A_11") (pintype "unspecified"))
      (node (ref "U7") (pin "28") (pinfunction "BCLK2_28") (pintype "unspecified"))
    )
    (net (code "8") (name "E5") (class "Default")
      (node (ref "U2") (pin "10") (pinfunction "B_10") (pintype "unspecified"))
      (node (ref "U7") (pin "27") (pinfunction "IN2_27") (pintype "unspecified"))
    )
    (net (code "9") (name "E6") (class "Default")
      (node (ref "U2") (pin "9") (pinfunction "C_9") (pintype "unspecified"))
      (node (ref "U7") (pin "26") (pinfunction "OUT1D_26") (pintype "unspecified"))
    )
    (net (code "10") (name "E7") (class "Default")
      (node (ref "U3") (pin "11") (pinfunction "A_11") (pintype "unspecified"))
      (node (ref "U7") (pin "25") (pinfunction "RX2_25") (pintype "unspecified"))
    )
    (net (code "11") (name "E8") (class "Default")
      (node (ref "U3") (pin "10") (pinfunction "B_10") (pintype "unspecified"))
      (node (ref "U7") (pin "24") (pinfunction "TX2_24") (pintype "unspecified"))
    )
    (net (code "12") (name "E9") (class "Default")
      (node (ref "U3") (pin "9") (pinfunction "C_9") (pintype "unspecified"))
      (node (ref "U7") (pin "23") (pinfunction "OUT1C_23") (pintype "unspecified"))
    )
    (net (code "13") (name "E10") (class "Default")
      (node (ref "U4") (pin "11") (pinfunction "A_11") (pintype "unspecified"))
      (node (ref "U7") (pin "22") (pinfunction "CS_22") (pintype "unspecified"))
    )
    (net (code "14") (name "E11") (class "Default")
      (node (ref "U4") (pin "10") (pinfunction "B_10") (pintype "unspecified"))
      (node (ref "U7") (pin "21") (pinfunction "MOSI_21") (pintype "unspecified"))
    )
    (net (code "15") (name "E12") (class "Default")
      (node (ref "U4") (pin "9") (pinfunction "C_9") (pintype "unspecified"))
      (node (ref "U7") (pin "20") (pinfunction "MISO_20") (pintype "unspecified"))
    )
    (net (code "16") (name "GND") (class "Default")
      (node (ref "C1") (pin "1") (pinfunction "1_1") (pintype "unspecified"))
      (node (ref "C2") (pin "1") (pinfunction "1_1") (pintype "unspecified"))
      (node (ref "C3") (pin "1") (pinfunction "1_1") (pintype "unspecified"))
      (node (ref "C4") (pin "1") (pinfunction "1_1") (pintype "unspecified"))
      (node (ref "C5") (pin "1") (pinfunction "1_1") (pintype "unspecified"))
      (node (ref "C6") (pin "1") (pinfunction "1_1") (pintype "unspecified"))
      (node (ref "R1") (pin "1") (pinfunction "1_1") (pintype "unspecified"))
      (node (ref "R10") (pin "1") (pinfunction "1_1") (pintype "unspecified"))
      (node (ref "R11") (pin "1") (pinfunction "1_1") (pintype "unspecified"))
      (node (ref "R12") (pin "1") (pinfunction "1_1") (pintype "unspecified"))
      (node (ref "R13") (pin "1") (pinfunction "1_1") (pintype "unspecified"))
      (node (ref "R14") (pin "1") (pinfunction "1_1") (pintype "unspecified"))
      (node (ref "R15") (pin "1") (pinfunction "1_1") (pintype "unspecified"))
      (node (ref "R16") (pin "1") (pinfunction "1_1") (pintype "unspecified"))
      (node (ref "R17") (pin "1") (pinfunction "1_1") (pintype "unspecified"))
      (node (ref "R18") (pin "1") (pinfunction "1_1") (pintype "unspecified"))
      (node (ref "R19") (pin "1") (pinfunction "1_1") (pintype "unspecified"))
      (node (ref "R2") (pin "1") (pinfunction "1_1") (pintype "unspecified"))
      (node (ref "R20") (pin "1") (pinfunction "1_1") (pintype "unspecified"))
      (node (ref "R21") (pin "1") (pinfunction "1_1") (pintype "unspecified"))
      (node (ref "R22") (pin "1") (pinfunction "1_1") (pintype "unspecified"))
      (node (ref "R23") (pin "1") (pinfunction "1_1") (pintype "unspecified"))
      (node (ref "R24") (pin "1") (pinfunction "1_1") (pintype "unspecified"))
      (node (ref "R25") (pin "1") (pinfunction "1_1") (pintype "unspecified"))
      (node (ref "R26") (pin "1") (pinfunction "1_1") (pintype "unspecified"))
      (node (ref "R27") (pin "1") (pinfunction "1_1") (pintype "unspecified"))
      (node (ref "R28") (pin "1") (pinfunction "1_1") (pintype "unspecified"))
      (node (ref "R29") (pin "1") (pinfunction "1_1") (pintype "unspecified"))
      (node (ref "R3") (pin "1") (pinfunction "1_1") (pintype "unspecified"))
      (node (ref "R30") (pin "1") (pinfunction "1_1") (pintype "unspecified"))
      (node (ref "R31") (pin "1") (pinfunction "1_1") (pintype "unspecified"))
      (node (ref "R32") (pin "1") (pinfunction "1_1") (pintype "unspecified"))
      (node (ref "R33") (pin "1") (pinfunction "1_1") (pintype "unspecified"))
      (node (ref "R34") (pin "1") (pinfunction "1_1") (pintype "unspecified"))
      (node (ref "R35") (pin "1") (pinfunction "1_1") (pintype "unspecified"))
      (node (ref "R36") (pin "1") (pinfunction "1_1") (pintype "unspecified"))
      (node (ref "R37") (pin "1") (pinfunction "1_1") (pintype "unspecified"))
      (node (ref "R38") (pin "1") (pinfunction "1_1") (pintype "unspecified"))
      (node (ref "R39") (pin "1") (pinfunction "1_1") (pintype "unspecified"))
      (node (ref "R4") (pin "1") (pinfunction "1_1") (pintype "unspecified"))
      (node (ref "R40") (pin "1") (pinfunction "1_1") (pintype "unspecified"))
      (node (ref "R41") (pin "1") (pinfunction "1_1") (pintype "unspecified"))
      (node (ref "R42") (pin "1") (pinfunction "1_1") (pintype "unspecified"))
      (node (ref "R43") (pin "1") (pinfunction "1_1") (pintype "unspecified"))
      (node (ref "R44") (pin "1") (pinfunction "1_1") (pintype "unspecified"))
      (node (ref "R45") (pin "1") (pinfunction "1_1") (pintype "unspecified"))
      (node (ref "R46") (pin "1") (pinfunction "1_1") (pintype "unspecified"))
      (node (ref "R47") (pin "1") (pinfunction "1_1") (pintype "unspecified"))
      (node (ref "R48") (pin "1") (pinfunction "1_1") (pintype "unspecified"))
      (node (ref "R49") (pin "1") (pinfunction "1_1") (pintype "unspecified"))
      (node (ref "R5") (pin "1") (pinfunction "1_1") (pintype "unspecified"))
      (node (ref "R50") (pin "1") (pinfunction "1_1") (pintype "unspecified"))
      (node (ref "R51") (pin "1") (pinfunction "1_1") (pintype "unspecified"))
      (node (ref "R52") (pin "1") (pinfunction "1_1") (pintype "unspecified"))
      (node (ref "R53") (pin "1") (pinfunction "1_1") (pintype "unspecified"))
      (node (ref "R54") (pin "1") (pinfunction "1_1") (pintype "unspecified"))
      (node (ref "R55") (pin "1") (pinfunction "1_1") (pintype "unspecified"))
      (node (ref "R56") (pin "1") (pinfunction "1_1") (pintype "unspecified"))
      (node (ref "R57") (pin "1") (pinfunction "1_1") (pintype "unspecified"))
      (node (ref "R58") (pin "1") (pinfunction "1_1") (pintype "unspecified"))
      (node (ref "R59") (pin "1") (pinfunction "1_1") (pintype "unspecified"))
      (node (ref "R6") (pin "1") (pinfunction "1_1") (pintype "unspecified"))
      (node (ref "R60") (pin "1") (pinfunction "1_1") (pintype "unspecified"))
      (node (ref "R61") (pin "1") (pinfunction "1_1") (pintype "unspecified"))
      (node (ref "R62") (pin "1") (pinfunction "1_1") (pintype "unspecified"))
      (node (ref "R63") (pin "1") (pinfunction "1_1") (pintype "unspecified"))
      (node (ref "R64") (pin "1") (pinfunction "1_1") (pintype "unspecified"))
      (node (ref "R7") (pin "1") (pinfunction "1_1") (pintype "unspecified"))
      (node (ref "R8") (pin "1") (pinfunction "1_1") (pintype "unspecified"))
      (node (ref "R9") (pin "1") (pinfunction "1_1") (pintype "unspecified"))
      (node (ref "U1") (pin "6") (pinfunction "INH_6") (pintype "unspecified"))
      (node (ref "U1") (pin "7") (pinfunction "VEE_7") (pintype "unspecified"))
      (node (ref "U1") (pin "8") (pinfunction "VSS_8") (pintype "unspecified"))
      (node (ref "U10") (pin "4") (pinfunction "4_4") (pintype "unspecified"))
      (node (ref "U11") (pin "4") (pinfunction "4_4") (pintype "unspecified"))
      (node (ref "U2") (pin "6") (pinfunction "INH_6") (pintype "unspecified"))
      (node (ref "U2") (pin "7") (pinfunction "VEE_7") (pintype "unspecified"))
      (node (ref "U2") (pin "8") (pinfunction "VSS_8") (pintype "unspecified"))
      (node (ref "U3") (pin "6") (pinfunction "INH_6") (pintype "unspecified"))
      (node (ref "U3") (pin "7") (pinfunction "VEE_7") (pintype "unspecified"))
      (node (ref "U3") (pin "8") (pinfunction "VSS_8") (pintype "unspecified"))
      (node (ref "U4") (pin "6") (pinfunction "INH_6") (pintype "unspecified"))
      (node (ref "U4") (pin "7") (pinfunction "VEE_7") (pintype "unspecified"))
      (node (ref "U4") (pin "8") (pinfunction "VSS_8") (pintype "unspecified"))
      (node (ref "U5") (pin "1") (pinfunction "GND_1") (pintype "unspecified"))
      (node (ref "U6") (pin "1") (pinfunction "GND_1") (pintype "unspecified"))
      (node (ref "U7") (pin "33") (pinfunction "GND_33") (pintype "unspecified"))
      (node (ref "U8") (pin "2") (pinfunction "GND_2") (pintype "unspecified"))
      (node (ref "U9") (pin "2") (pinfunction "GND_2") (pintype "unspecified"))
      (node (ref "XP1") (pin "1") (pinfunction "1_1") (pintype "unspecified"))
    )
    (net (code "17") (name "Net-(D1--)") (class "Default")
      (node (ref "D1") (pin "1") (pinfunction "-_1") (pintype "unspecified"))
      (node (ref "U8") (pin "3") (pinfunction "IN_3") (pintype "unspecified"))
    )
    (net (code "18") (name "Net-(D2--)") (class "Default")
      (node (ref "D2") (pin "1") (pinfunction "-_1") (pintype "unspecified"))
      (node (ref "U9") (pin "3") (pinfunction "IN_3") (pintype "unspecified"))
    )
    (net (code "19") (name "Net-(LED1-C)") (class "Default")
      (node (ref "LED1") (pin "2") (pinfunction "C_2") (pintype "unspecified"))
      (node (ref "R1") (pin "2") (pinfunction "2_2") (pintype "unspecified"))
    )
    (net (code "20") (name "Net-(LED2-C)") (class "Default")
      (node (ref "LED2") (pin "2") (pinfunction "C_2") (pintype "unspecified"))
      (node (ref "R2") (pin "2") (pinfunction "2_2") (pintype "unspecified"))
    )
    (net (code "21") (name "Net-(LED3-C)") (class "Default")
      (node (ref "LED3") (pin "2") (pinfunction "C_2") (pintype "unspecified"))
      (node (ref "R3") (pin "2") (pinfunction "2_2") (pintype "unspecified"))
    )
    (net (code "22") (name "Net-(LED4-C)") (class "Default")
      (node (ref "LED4") (pin "2") (pinfunction "C_2") (pintype "unspecified"))
      (node (ref "R4") (pin "2") (pinfunction "2_2") (pintype "unspecified"))
    )
    (net (code "23") (name "Net-(LED5-C)") (class "Default")
      (node (ref "LED5") (pin "2") (pinfunction "C_2") (pintype "unspecified"))
      (node (ref "R5") (pin "2") (pinfunction "2_2") (pintype "unspecified"))
    )
    (net (code "24") (name "Net-(LED6-C)") (class "Default")
      (node (ref "LED6") (pin "2") (pinfunction "C_2") (pintype "unspecified"))
      (node (ref "R6") (pin "2") (pinfunction "2_2") (pintype "unspecified"))
    )
    (net (code "25") (name "Net-(LED7-C)") (class "Default")
      (node (ref "LED7") (pin "2") (pinfunction "C_2") (pintype "unspecified"))
      (node (ref "R7") (pin "2") (pinfunction "2_2") (pintype "unspecified"))
    )
    (net (code "26") (name "Net-(LED8-C)") (class "Default")
      (node (ref "LED8") (pin "2") (pinfunction "C_2") (pintype "unspecified"))
      (node (ref "R8") (pin "2") (pinfunction "2_2") (pintype "unspecified"))
    )
    (net (code "27") (name "Net-(LED9-C)") (class "Default")
      (node (ref "LED9") (pin "2") (pinfunction "C_2") (pintype "unspecified"))
      (node (ref "R9") (pin "2") (pinfunction "2_2") (pintype "unspecified"))
    )
    (net (code "28") (name "Net-(LED10-C)") (class "Default")
      (node (ref "LED10") (pin "2") (pinfunction "C_2") (pintype "unspecified"))
      (node (ref "R10") (pin "2") (pinfunction "2_2") (pintype "unspecified"))
    )
    (net (code "29") (name "Net-(LED11-C)") (class "Default")
      (node (ref "LED11") (pin "2") (pinfunction "C_2") (pintype "unspecified"))
      (node (ref "R11") (pin "2") (pinfunction "2_2") (pintype "unspecified"))
    )
    (net (code "30") (name "Net-(LED12-C)") (class "Default")
      (node (ref "LED12") (pin "2") (pinfunction "C_2") (pintype "unspecified"))
      (node (ref "R12") (pin "2") (pinfunction "2_2") (pintype "unspecified"))
    )
    (net (code "31") (name "Net-(LED13-C)") (class "Default")
      (node (ref "LED13") (pin "2") (pinfunction "C_2") (pintype "unspecified"))
      (node (ref "R13") (pin "2") (pinfunction "2_2") (pintype "unspecified"))
    )
    (net (code "32") (name "Net-(LED14-C)") (class "Default")
      (node (ref "LED14") (pin "2") (pinfunction "C_2") (pintype "unspecified"))
      (node (ref "R14") (pin "2") (pinfunction "2_2") (pintype "unspecified"))
    )
    (net (code "33") (name "Net-(LED15-C)") (class "Default")
      (node (ref "LED15") (pin "2") (pinfunction "C_2") (pintype "unspecified"))
      (node (ref "R15") (pin "2") (pinfunction "2_2") (pintype "unspecified"))
    )
    (net (code "34") (name "Net-(LED16-C)") (class "Default")
      (node (ref "LED16") (pin "2") (pinfunction "C_2") (pintype "unspecified"))
      (node (ref "R16") (pin "2") (pinfunction "2_2") (pintype "unspecified"))
    )
    (net (code "35") (name "Net-(LED17-C)") (class "Default")
      (node (ref "LED17") (pin "2") (pinfunction "C_2") (pintype "unspecified"))
      (node (ref "R17") (pin "2") (pinfunction "2_2") (pintype "unspecified"))
    )
    (net (code "36") (name "Net-(LED18-C)") (class "Default")
      (node (ref "LED18") (pin "2") (pinfunction "C_2") (pintype "unspecified"))
      (node (ref "R18") (pin "2") (pinfunction "2_2") (pintype "unspecified"))
    )
    (net (code "37") (name "Net-(LED19-C)") (class "Default")
      (node (ref "LED19") (pin "2") (pinfunction "C_2") (pintype "unspecified"))
      (node (ref "R19") (pin "2") (pinfunction "2_2") (pintype "unspecified"))
    )
    (net (code "38") (name "Net-(LED20-C)") (class "Default")
      (node (ref "LED20") (pin "2") (pinfunction "C_2") (pintype "unspecified"))
      (node (ref "R20") (pin "2") (pinfunction "2_2") (pintype "unspecified"))
    )
    (net (code "39") (name "Net-(LED21-C)") (class "Default")
      (node (ref "LED21") (pin "2") (pinfunction "C_2") (pintype "unspecified"))
      (node (ref "R21") (pin "2") (pinfunction "2_2") (pintype "unspecified"))
    )
    (net (code "40") (name "Net-(LED22-C)") (class "Default")
      (node (ref "LED22") (pin "2") (pinfunction "C_2") (pintype "unspecified"))
      (node (ref "R22") (pin "2") (pinfunction "2_2") (pintype "unspecified"))
    )
    (net (code "41") (name "Net-(LED23-C)") (class "Default")
      (node (ref "LED23") (pin "2") (pinfunction "C_2") (pintype "unspecified"))
      (node (ref "R23") (pin "2") (pinfunction "2_2") (pintype "unspecified"))
    )
    (net (code "42") (name "Net-(LED24-C)") (class "Default")
      (node (ref "LED24") (pin "2") (pinfunction "C_2") (pintype "unspecified"))
      (node (ref "R24") (pin "2") (pinfunction "2_2") (pintype "unspecified"))
    )
    (net (code "43") (name "Net-(LED25-C)") (class "Default")
      (node (ref "LED25") (pin "2") (pinfunction "C_2") (pintype "unspecified"))
      (node (ref "R25") (pin "2") (pinfunction "2_2") (pintype "unspecified"))
    )
    (net (code "44") (name "Net-(LED26-C)") (class "Default")
      (node (ref "LED26") (pin "2") (pinfunction "C_2") (pintype "unspecified"))
      (node (ref "R26") (pin "2") (pinfunction "2_2") (pintype "unspecified"))
    )
    (net (code "45") (name "Net-(LED27-C)") (class "Default")
      (node (ref "LED27") (pin "2") (pinfunction "C_2") (pintype "unspecified"))
      (node (ref "R27") (pin "2") (pinfunction "2_2") (pintype "unspecified"))
    )
    (net (code "46") (name "Net-(LED28-C)") (class "Default")
      (node (ref "LED28") (pin "2") (pinfunction "C_2") (pintype "unspecified"))
      (node (ref "R28") (pin "2") (pinfunction "2_2") (pintype "unspecified"))
    )
    (net (code "47") (name "Net-(LED29-C)") (class "Default")
      (node (ref "LED29") (pin "2") (pinfunction "C_2") (pintype "unspecified"))
      (node (ref "R29") (pin "2") (pinfunction "2_2") (pintype "unspecified"))
    )
    (net (code "48") (name "Net-(LED30-C)") (class "Default")
      (node (ref "LED30") (pin "2") (pinfunction "C_2") (pintype "unspecified"))
      (node (ref "R30") (pin "2") (pinfunction "2_2") (pintype "unspecified"))
    )
    (net (code "49") (name "Net-(LED31-C)") (class "Default")
      (node (ref "LED31") (pin "2") (pinfunction "C_2") (pintype "unspecified"))
      (node (ref "R31") (pin "2") (pinfunction "2_2") (pintype "unspecified"))
    )
    (net (code "50") (name "Net-(LED32-C)") (class "Default")
      (node (ref "LED32") (pin "2") (pinfunction "C_2") (pintype "unspecified"))
      (node (ref "R32") (pin "2") (pinfunction "2_2") (pintype "unspecified"))
    )
    (net (code "51") (name "O1") (class "Default")
      (node (ref "U1") (pin "3") (pinfunction "COMOUT/IN_3") (pintype "unspecified"))
      (node (ref "U7") (pin "13") (pinfunction "A0_13") (pintype "unspecified"))
    )
    (net (code "52") (name "O2") (class "Default")
      (node (ref "U2") (pin "3") (pinfunction "COMOUT/IN_3") (pintype "unspecified"))
      (node (ref "U7") (pin "12") (pinfunction "A1_12") (pintype "unspecified"))
    )
    (net (code "53") (name "O3") (class "Default")
      (node (ref "U3") (pin "3") (pinfunction "COMOUT/IN_3") (pintype "unspecified"))
      (node (ref "U7") (pin "5") (pinfunction "A8_5") (pintype "unspecified"))
    )
    (net (code "54") (name "O4") (class "Default")
      (node (ref "U4") (pin "3") (pinfunction "COMOUT/IN_3") (pintype "unspecified"))
      (node (ref "U7") (pin "4") (pinfunction "A9_4") (pintype "unspecified"))
    )
    (net (code "55") (name "RX1") (class "Default")
      (node (ref "U11") (pin "2") (pinfunction "2_2") (pintype "unspecified"))
      (node (ref "U7") (pin "32") (pinfunction "RX1_32") (pintype "unspecified"))
    )
    (net (code "56") (name "RX5") (class "Default")
      (node (ref "U10") (pin "2") (pinfunction "2_2") (pintype "unspecified"))
      (node (ref "U7") (pin "6") (pinfunction "A7_6") (pintype "unspecified"))
    )
    (net (code "57") (name "S1") (class "Default")
      (node (ref "F1") (pin "2") (pinfunction "E_2") (pintype "input"))
      (node (ref "R33") (pin "2") (pinfunction "2_2") (pintype "unspecified"))
      (node (ref "U1") (pin "12") (pinfunction "CH3IN/OUT_12") (pintype "unspecified"))
    )
    (net (code "58") (name "S2") (class "Default")
      (node (ref "F2") (pin "2") (pinfunction "E_2") (pintype "input"))
      (node (ref "R34") (pin "2") (pinfunction "2_2") (pintype "unspecified"))
      (node (ref "U1") (pin "13") (pinfunction "CH0IN/OUT_13") (pintype "unspecified"))
    )
    (net (code "59") (name "S3") (class "Default")
      (node (ref "F3") (pin "2") (pinfunction "E_2") (pintype "input"))
      (node (ref "R35") (pin "2") (pinfunction "2_2") (pintype "unspecified"))
      (node (ref "U1") (pin "14") (pinfunction "CH1IN/OUT_14") (pintype "unspecified"))
    )
    (net (code "60") (name "S4") (class "Default")
      (node (ref "F4") (pin "2") (pinfunction "E_2") (pintype "input"))
      (node (ref "R36") (pin "2") (pinfunction "2_2") (pintype "unspecified"))
      (node (ref "U1") (pin "15") (pinfunction "CH2IN/OUT_15") (pintype "unspecified"))
    )
    (net (code "61") (name "S5") (class "Default")
      (node (ref "F5") (pin "2") (pinfunction "E_2") (pintype "input"))
      (node (ref "R37") (pin "2") (pinfunction "2_2") (pintype "unspecified"))
      (node (ref "U1") (pin "5") (pinfunction "CH5IN/OUT_5") (pintype "unspecified"))
    )
    (net (code "62") (name "S6") (class "Default")
      (node (ref "F6") (pin "2") (pinfunction "E_2") (pintype "input"))
      (node (ref "R38") (pin "2") (pinfunction "2_2") (pintype "unspecified"))
      (node (ref "U1") (pin "4") (pinfunction "CH7IN/OUT_4") (pintype "unspecified"))
    )
    (net (code "63") (name "S7") (class "Default")
      (node (ref "F7") (pin "2") (pinfunction "E_2") (pintype "input"))
      (node (ref "R39") (pin "2") (pinfunction "2_2") (pintype "unspecified"))
      (node (ref "U1") (pin "2") (pinfunction "CH6IN/OUT_2") (pintype "unspecified"))
    )
    (net (code "64") (name "S8") (class "Default")
      (node (ref "F8") (pin "2") (pinfunction "E_2") (pintype "input"))
      (node (ref "R40") (pin "2") (pinfunction "2_2") (pintype "unspecified"))
      (node (ref "U1") (pin "1") (pinfunction "CH4IN/OUT_1") (pintype "unspecified"))
    )
    (net (code "65") (name "S9") (class "Default")
      (node (ref "F9") (pin "2") (pinfunction "E_2") (pintype "input"))
      (node (ref "R41") (pin "2") (pinfunction "2_2") (pintype "unspecified"))
      (node (ref "U2") (pin "12") (pinfunction "CH3IN/OUT_12") (pintype "unspecified"))
    )
    (net (code "66") (name "S10") (class "Default")
      (node (ref "F10") (pin "2") (pinfunction "E_2") (pintype "input"))
      (node (ref "R42") (pin "2") (pinfunction "2_2") (pintype "unspecified"))
      (node (ref "U2") (pin "13") (pinfunction "CH0IN/OUT_13") (pintype "unspecified"))
    )
    (net (code "67") (name "S11") (class "Default")
      (node (ref "F11") (pin "2") (pinfunction "E_2") (pintype "input"))
      (node (ref "R43") (pin "2") (pinfunction "2_2") (pintype "unspecified"))
      (node (ref "U2") (pin "14") (pinfunction "CH1IN/OUT_14") (pintype "unspecified"))
    )
    (net (code "68") (name "S12") (class "Default")
      (node (ref "F12") (pin "2") (pinfunction "E_2") (pintype "input"))
      (node (ref "R44") (pin "2") (pinfunction "2_2") (pintype "unspecified"))
      (node (ref "U2") (pin "15") (pinfunction "CH2IN/OUT_15") (pintype "unspecified"))
    )
    (net (code "69") (name "S13") (class "Default")
      (node (ref "F13") (pin "2") (pinfunction "E_2") (pintype "input"))
      (node (ref "R45") (pin "2") (pinfunction "2_2") (pintype "unspecified"))
      (node (ref "U2") (pin "5") (pinfunction "CH5IN/OUT_5") (pintype "unspecified"))
    )
    (net (code "70") (name "S14") (class "Default")
      (node (ref "F14") (pin "2") (pinfunction "E_2") (pintype "input"))
      (node (ref "R46") (pin "2") (pinfunction "2_2") (pintype "unspecified"))
      (node (ref "U2") (pin "4") (pinfunction "CH7IN/OUT_4") (pintype "unspecified"))
    )
    (net (code "71") (name "S15") (class "Default")
      (node (ref "F15") (pin "2") (pinfunction "E_2") (pintype "input"))
      (node (ref "R47") (pin "2") (pinfunction "2_2") (pintype "unspecified"))
      (node (ref "U2") (pin "2") (pinfunction "CH6IN/OUT_2") (pintype "unspecified"))
    )
    (net (code "72") (name "S16") (class "Default")
      (node (ref "F16") (pin "2") (pinfunction "E_2") (pintype "input"))
      (node (ref "R48") (pin "2") (pinfunction "2_2") (pintype "unspecified"))
      (node (ref "U2") (pin "1") (pinfunction "CH4IN/OUT_1") (pintype "unspecified"))
    )
    (net (code "73") (name "S17") (class "Default")
      (node (ref "F17") (pin "2") (pinfunction "E_2") (pintype "input"))
      (node (ref "R49") (pin "2") (pinfunction "2_2") (pintype "unspecified"))
      (node (ref "U3") (pin "12") (pinfunction "CH3IN/OUT_12") (pintype "unspecified"))
    )
    (net (code "74") (name "S18") (class "Default")
      (node (ref "F18") (pin "2") (pinfunction "E_2") (pintype "input"))
      (node (ref "R50") (pin "2") (pinfunction "2_2") (pintype "unspecified"))
      (node (ref "U3") (pin "13") (pinfunction "CH0IN/OUT_13") (pintype "unspecified"))
    )
    (net (code "75") (name "S19") (class "Default")
      (node (ref "F19") (pin "2") (pinfunction "E_2") (pintype "input"))
      (node (ref "R51") (pin "2") (pinfunction "2_2") (pintype "unspecified"))
      (node (ref "U3") (pin "14") (pinfunction "CH1IN/OUT_14") (pintype "unspecified"))
    )
    (net (code "76") (name "S20") (class "Default")
      (node (ref "F20") (pin "2") (pinfunction "E_2") (pintype "input"))
      (node (ref "R52") (pin "2") (pinfunction "2_2") (pintype "unspecified"))
      (node (ref "U3") (pin "15") (pinfunction "CH2IN/OUT_15") (pintype "unspecified"))
    )
    (net (code "77") (name "S21") (class "Default")
      (node (ref "F21") (pin "2") (pinfunction "E_2") (pintype "input"))
      (node (ref "R53") (pin "2") (pinfunction "2_2") (pintype "unspecified"))
      (node (ref "U3") (pin "5") (pinfunction "CH5IN/OUT_5") (pintype "unspecified"))
    )
    (net (code "78") (name "S22") (class "Default")
      (node (ref "F22") (pin "2") (pinfunction "E_2") (pintype "input"))
      (node (ref "R54") (pin "2") (pinfunction "2_2") (pintype "unspecified"))
      (node (ref "U3") (pin "4") (pinfunction "CH7IN/OUT_4") (pintype "unspecified"))
    )
    (net (code "79") (name "S23") (class "Default")
      (node (ref "F23") (pin "2") (pinfunction "E_2") (pintype "input"))
      (node (ref "R55") (pin "2") (pinfunction "2_2") (pintype "unspecified"))
      (node (ref "U3") (pin "2") (pinfunction "CH6IN/OUT_2") (pintype "unspecified"))
    )
    (net (code "80") (name "S24") (class "Default")
      (node (ref "F24") (pin "2") (pinfunction "E_2") (pintype "input"))
      (node (ref "R56") (pin "2") (pinfunction "2_2") (pintype "unspecified"))
      (node (ref "U3") (pin "1") (pinfunction "CH4IN/OUT_1") (pintype "unspecified"))
    )
    (net (code "81") (name "S25") (class "Default")
      (node (ref "F25") (pin "2") (pinfunction "E_2") (pintype "input"))
      (node (ref "R57") (pin "2") (pinfunction "2_2") (pintype "unspecified"))
      (node (ref "U4") (pin "12") (pinfunction "CH3IN/OUT_12") (pintype "unspecified"))
    )
    (net (code "82") (name "S26") (class "Default")
      (node (ref "F26") (pin "2") (pinfunction "E_2") (pintype "input"))
      (node (ref "R58") (pin "2") (pinfunction "2_2") (pintype "unspecified"))
      (node (ref "U4") (pin "13") (pinfunction "CH0IN/OUT_13") (pintype "unspecified"))
    )
    (net (code "83") (name "S27") (class "Default")
      (node (ref "F27") (pin "2") (pinfunction "E_2") (pintype "input"))
      (node (ref "R59") (pin "2") (pinfunction "2_2") (pintype "unspecified"))
      (node (ref "U4") (pin "14") (pinfunction "CH1IN/OUT_14") (pintype "unspecified"))
    )
    (net (code "84") (name "S28") (class "Default")
      (node (ref "F28") (pin "2") (pinfunction "E_2") (pintype "input"))
      (node (ref "R60") (pin "2") (pinfunction "2_2") (pintype "unspecified"))
      (node (ref "U4") (pin "15") (pinfunction "CH2IN/OUT_15") (pintype "unspecified"))
    )
    (net (code "85") (name "S29") (class "Default")
      (node (ref "F29") (pin "2") (pinfunction "E_2") (pintype "input"))
      (node (ref "R61") (pin "2") (pinfunction "2_2") (pintype "unspecified"))
      (node (ref "U4") (pin "5") (pinfunction "CH5IN/OUT_5") (pintype "unspecified"))
    )
    (net (code "86") (name "S30") (class "Default")
      (node (ref "F30") (pin "2") (pinfunction "E_2") (pintype "input"))
      (node (ref "R62") (pin "2") (pinfunction "2_2") (pintype "unspecified"))
      (node (ref "U4") (pin "4") (pinfunction "CH7IN/OUT_4") (pintype "unspecified"))
    )
    (net (code "87") (name "S31") (class "Default")
      (node (ref "F31") (pin "2") (pinfunction "E_2") (pintype "input"))
      (node (ref "R63") (pin "2") (pinfunction "2_2") (pintype "unspecified"))
      (node (ref "U4") (pin "2") (pinfunction "CH6IN/OUT_2") (pintype "unspecified"))
    )
    (net (code "88") (name "S32") (class "Default")
      (node (ref "F32") (pin "2") (pinfunction "E_2") (pintype "input"))
      (node (ref "R64") (pin "2") (pinfunction "2_2") (pintype "unspecified"))
      (node (ref "U4") (pin "1") (pinfunction "CH4IN/OUT_1") (pintype "unspecified"))
    )
    (net (code "89") (name "SCL1") (class "Default")
      (node (ref "U5") (pin "4") (pinfunction "SCL_4") (pintype "unspecified"))
      (node (ref "U7") (pin "8") (pinfunction "A5_8") (pintype "unspecified"))
    )
    (net (code "90") (name "SCL2") (class "Default")
      (node (ref "U6") (pin "4") (pinfunction "SCL_4") (pintype "unspecified"))
      (node (ref "U7") (pin "11") (pinfunction "A2_11") (pintype "unspecified"))
    )
    (net (code "91") (name "SDA1") (class "Default")
      (node (ref "U5") (pin "3") (pinfunction "SDA_3") (pintype "unspecified"))
      (node (ref "U7") (pin "9") (pinfunction "A4_9") (pintype "unspecified"))
    )
    (net (code "92") (name "SDA2") (class "Default")
      (node (ref "U6") (pin "3") (pinfunction "SDA_3") (pintype "unspecified"))
      (node (ref "U7") (pin "10") (pinfunction "A3_10") (pintype "unspecified"))
    )
    (net (code "93") (name "TX1") (class "Default")
      (node (ref "U11") (pin "3") (pinfunction "3_3") (pintype "unspecified"))
      (node (ref "U7") (pin "31") (pinfunction "TX1_31") (pintype "unspecified"))
    )
    (net (code "94") (name "TX5") (class "Default")
      (node (ref "U10") (pin "3") (pinfunction "3_3") (pintype "unspecified"))
      (node (ref "U7") (pin "7") (pinfunction "A6_7") (pintype "unspecified"))
    )
    (net (code "95") (name "unconnected-(U5-IO9-Pad5)") (class "Default")
      (node (ref "U5") (pin "5") (pinfunction "IO9_5") (pintype "unspecified+no_connect"))
    )
    (net (code "96") (name "unconnected-(U5-IO10-Pad6)") (class "Default")
      (node (ref "U5") (pin "6") (pinfunction "IO10_6") (pintype "unspecified+no_connect"))
    )
    (net (code "97") (name "unconnected-(U6-IO9-Pad5)") (class "Default")
      (node (ref "U6") (pin "5") (pinfunction "IO9_5") (pintype "unspecified+no_connect"))
    )
    (net (code "98") (name "unconnected-(U6-IO10-Pad6)") (class "Default")
      (node (ref "U6") (pin "6") (pinfunction "IO10_6") (pintype "unspecified+no_connect"))
    )
    (net (code "99") (name "unconnected-(U7-3.3V-Pad3)") (class "Default")
      (node (ref "U7") (pin "3") (pinfunction "3.3V_3") (pintype "unspecified+no_connect"))
    )
    (net (code "100") (name "unconnected-(U7-3.3V-Pad18)") (class "Default")
      (node (ref "U7") (pin "18") (pinfunction "3.3V_18") (pintype "unspecified+no_connect"))
    )
    (net (code "101") (name "unconnected-(U7-GND-Pad2)") (class "Default")
      (node (ref "U7") (pin "2") (pinfunction "GND_2") (pintype "unspecified+no_connect"))
    )
    (net (code "102") (name "unconnected-(U7-GND-Pad17)") (class "Default")
      (node (ref "U7") (pin "17") (pinfunction "GND_17") (pintype "unspecified+no_connect"))
    )
    (net (code "103") (name "unconnected-(U7-NC-Pad34)") (class "Default")
      (node (ref "U7") (pin "34") (pinfunction "NC_34") (pintype "unspecified+no_connect"))
    )
    (net (code "104") (name "unconnected-(U7-Program-Pad16)") (class "Default")
      (node (ref "U7") (pin "16") (pinfunction "Program_16") (pintype "unspecified+no_connect"))
    )
    (net (code "105") (name "unconnected-(U7-VBat-Pad19)") (class "Default")
      (node (ref "U7") (pin "19") (pinfunction "VBat_19") (pintype "unspecified+no_connect"))
    )
    (net (code "106") (name "unconnected-(U7-on{slash}Off-Pad15)") (class "Default")
      (node (ref "U7") (pin "15") (pinfunction "on/Off_15") (pintype "unspecified+no_connect"))
    )
    (net (code "107") (name "unconnected-(U8-EN-Pad4)") (class "Default")
      (node (ref "U8") (pin "4") (pinfunction "EN_4") (pintype "unspecified+no_connect"))
    )
    (net (code "108") (name "unconnected-(U9-EN-Pad4)") (class "Default")
      (node (ref "U9") (pin "4") (pinfunction "EN_4") (pintype "unspecified+no_connect"))
    )
  )
)
